# vewa-lfos.net
KiCad netlist of a schematic drawn in EAGLE
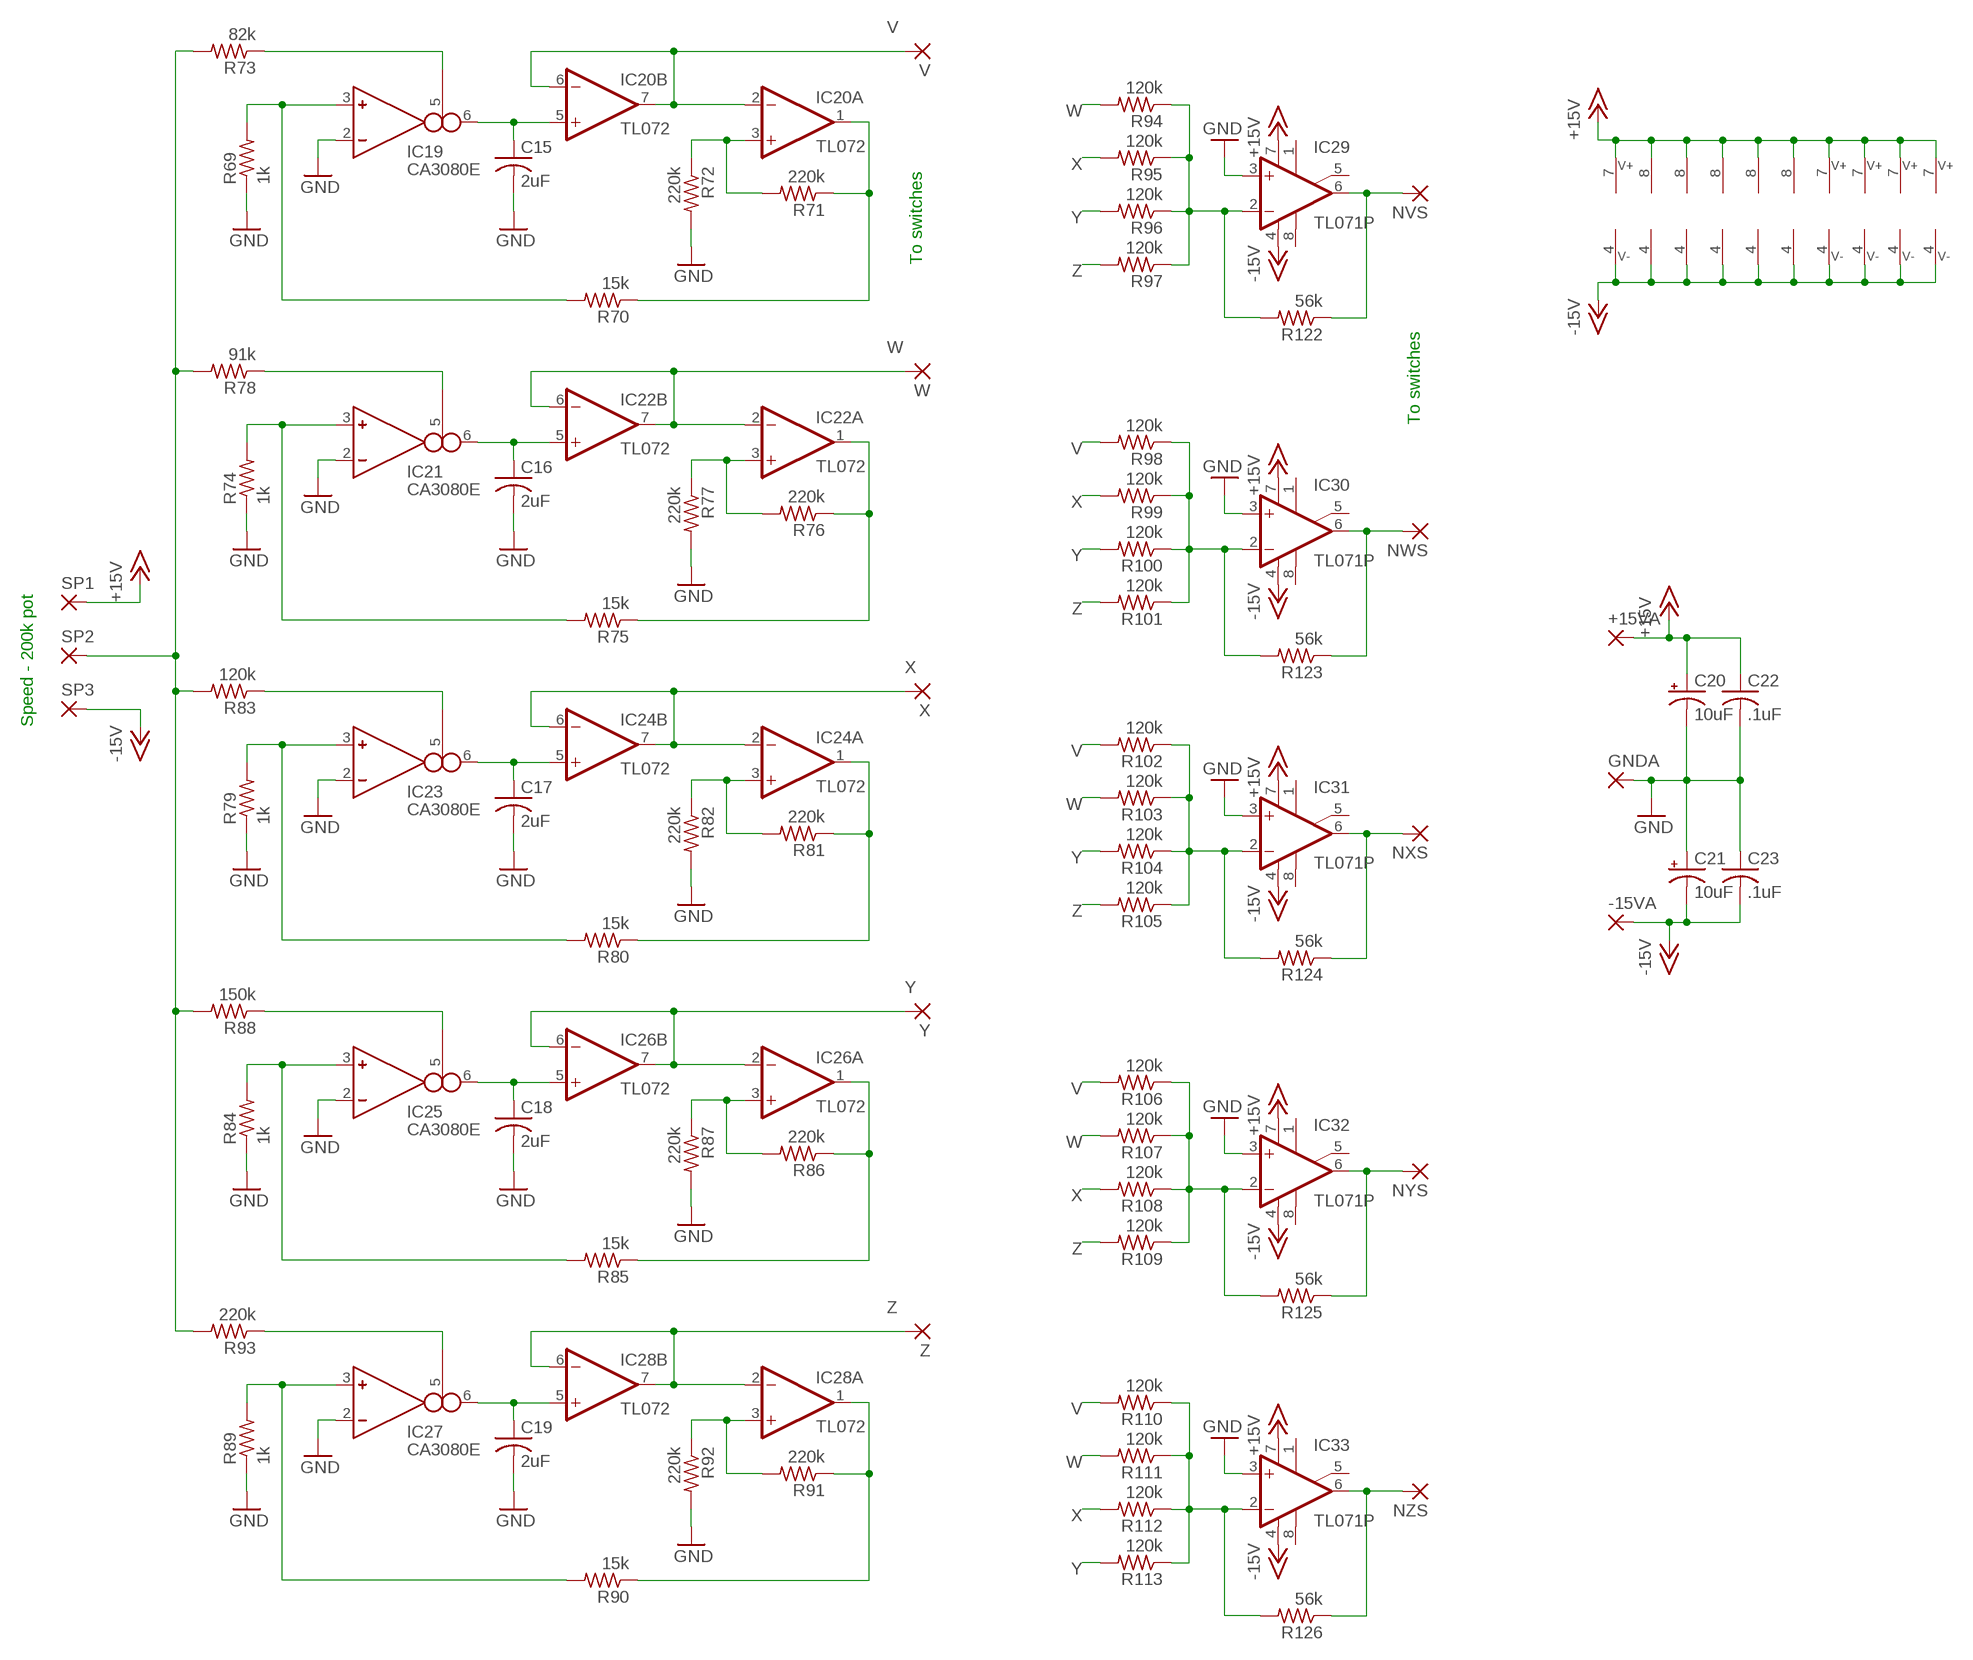
[diagram p0: schematic, sheet 1]

(export (version "E")
  (design (tool "Eeschema 10.0.6"))
  (components
    (comp (ref "+15VA")
      (value "2,54/1,0")
      (footprint "eagle-import:2,54_1,0")
      (libsource (lib "eagle-import") (part "2,54/1,0"))
    )
    (comp (ref "-15VA")
      (value "2,54/1,0")
      (footprint "eagle-import:2,54_1,0")
      (libsource (lib "eagle-import") (part "2,54/1,0"))
    )
    (comp (ref "C15")
      (value "2uF")
      (footprint "eagle-import:C050-025X075")
      (libsource (lib "eagle-import") (part "C-US050-025X075"))
    )
    (comp (ref "C16")
      (value "2uF")
      (footprint "eagle-import:C050-025X075")
      (libsource (lib "eagle-import") (part "C-US050-025X075"))
    )
    (comp (ref "C17")
      (value "2uF")
      (footprint "eagle-import:C050-025X075")
      (libsource (lib "eagle-import") (part "C-US050-025X075"))
    )
    (comp (ref "C18")
      (value "2uF")
      (footprint "eagle-import:C050-025X075")
      (libsource (lib "eagle-import") (part "C-US050-025X075"))
    )
    (comp (ref "C19")
      (value "2uF")
      (footprint "eagle-import:C050-025X075")
      (libsource (lib "eagle-import") (part "C-US050-025X075"))
    )
    (comp (ref "C20")
      (value "10uF")
      (footprint "eagle-import:E2,5-5")
      (libsource (lib "eagle-import") (part "CPOL-USE2.5-5"))
    )
    (comp (ref "C21")
      (value "10uF")
      (footprint "eagle-import:E2,5-5")
      (libsource (lib "eagle-import") (part "CPOL-USE2.5-5"))
    )
    (comp (ref "C22")
      (value ".1uF")
      (footprint "eagle-import:C050-025X075")
      (libsource (lib "eagle-import") (part "C-US050-025X075"))
    )
    (comp (ref "C23")
      (value ".1uF")
      (footprint "eagle-import:C050-025X075")
      (libsource (lib "eagle-import") (part "C-US050-025X075"))
    )
    (comp (ref "GNDA")
      (value "2,54/1,0")
      (footprint "eagle-import:2,54_1,0")
      (libsource (lib "eagle-import") (part "2,54/1,0"))
    )
    (comp (ref "IC19")
      (value "CA3080E")
      (footprint "eagle-import:DIL08")
      (libsource (lib "eagle-import") (part "CA3080E"))
    )
    (comp (ref "IC20")
      (value "TL072")
      (footprint "eagle-import:DIL08")
      (libsource (lib "eagle-import") (part "TL072-TOPP"))
    )
    (comp (ref "IC21")
      (value "CA3080E")
      (footprint "eagle-import:DIL08")
      (libsource (lib "eagle-import") (part "CA3080E"))
    )
    (comp (ref "IC22")
      (value "TL072")
      (footprint "eagle-import:DIL08")
      (libsource (lib "eagle-import") (part "TL072-TOPP"))
    )
    (comp (ref "IC23")
      (value "CA3080E")
      (footprint "eagle-import:DIL08")
      (libsource (lib "eagle-import") (part "CA3080E"))
    )
    (comp (ref "IC24")
      (value "TL072")
      (footprint "eagle-import:DIL08")
      (libsource (lib "eagle-import") (part "TL072-TOPP"))
    )
    (comp (ref "IC25")
      (value "CA3080E")
      (footprint "eagle-import:DIL08")
      (libsource (lib "eagle-import") (part "CA3080E"))
    )
    (comp (ref "IC26")
      (value "TL072")
      (footprint "eagle-import:DIL08")
      (libsource (lib "eagle-import") (part "TL072-TOPP"))
    )
    (comp (ref "IC27")
      (value "CA3080E")
      (footprint "eagle-import:DIL08")
      (libsource (lib "eagle-import") (part "CA3080E"))
    )
    (comp (ref "IC28")
      (value "TL072")
      (footprint "eagle-import:DIL08")
      (libsource (lib "eagle-import") (part "TL072-TOPP"))
    )
    (comp (ref "IC29")
      (value "TL071P")
      (footprint "eagle-import:DIL08")
      (libsource (lib "eagle-import") (part "TL071P"))
    )
    (comp (ref "IC30")
      (value "TL071P")
      (footprint "eagle-import:DIL08")
      (libsource (lib "eagle-import") (part "TL071P"))
    )
    (comp (ref "IC31")
      (value "TL071P")
      (footprint "eagle-import:DIL08")
      (libsource (lib "eagle-import") (part "TL071P"))
    )
    (comp (ref "IC32")
      (value "TL071P")
      (footprint "eagle-import:DIL08")
      (libsource (lib "eagle-import") (part "TL071P"))
    )
    (comp (ref "IC33")
      (value "TL071P")
      (footprint "eagle-import:DIL08")
      (libsource (lib "eagle-import") (part "TL071P"))
    )
    (comp (ref "NVS")
      (value "2,54/1,0")
      (footprint "eagle-import:2,54_1,0")
      (libsource (lib "eagle-import") (part "2,54/1,0"))
    )
    (comp (ref "NWS")
      (value "2,54/1,0")
      (footprint "eagle-import:2,54_1,0")
      (libsource (lib "eagle-import") (part "2,54/1,0"))
    )
    (comp (ref "NXS")
      (value "2,54/1,0")
      (footprint "eagle-import:2,54_1,0")
      (libsource (lib "eagle-import") (part "2,54/1,0"))
    )
    (comp (ref "NYS")
      (value "2,54/1,0")
      (footprint "eagle-import:2,54_1,0")
      (libsource (lib "eagle-import") (part "2,54/1,0"))
    )
    (comp (ref "NZS")
      (value "2,54/1,0")
      (footprint "eagle-import:2,54_1,0")
      (libsource (lib "eagle-import") (part "2,54/1,0"))
    )
    (comp (ref "R69")
      (value "1k")
      (footprint "eagle-import:0207_10")
      (libsource (lib "eagle-import") (part "R-US_0207/10"))
    )
    (comp (ref "R70")
      (value "15k")
      (footprint "eagle-import:0207_10")
      (libsource (lib "eagle-import") (part "R-US_0207/10"))
    )
    (comp (ref "R71")
      (value "220k")
      (footprint "eagle-import:0207_10")
      (libsource (lib "eagle-import") (part "R-US_0207/10"))
    )
    (comp (ref "R72")
      (value "220k")
      (footprint "eagle-import:0207_10")
      (libsource (lib "eagle-import") (part "R-US_0207/10"))
    )
    (comp (ref "R73")
      (value "82k")
      (footprint "eagle-import:0207_10")
      (libsource (lib "eagle-import") (part "R-US_0207/10"))
    )
    (comp (ref "R74")
      (value "1k")
      (footprint "eagle-import:0207_10")
      (libsource (lib "eagle-import") (part "R-US_0207/10"))
    )
    (comp (ref "R75")
      (value "15k")
      (footprint "eagle-import:0207_10")
      (libsource (lib "eagle-import") (part "R-US_0207/10"))
    )
    (comp (ref "R76")
      (value "220k")
      (footprint "eagle-import:0207_10")
      (libsource (lib "eagle-import") (part "R-US_0207/10"))
    )
    (comp (ref "R77")
      (value "220k")
      (footprint "eagle-import:0207_10")
      (libsource (lib "eagle-import") (part "R-US_0207/10"))
    )
    (comp (ref "R78")
      (value "91k")
      (footprint "eagle-import:0207_10")
      (libsource (lib "eagle-import") (part "R-US_0207/10"))
    )
    (comp (ref "R79")
      (value "1k")
      (footprint "eagle-import:0207_10")
      (libsource (lib "eagle-import") (part "R-US_0207/10"))
    )
    (comp (ref "R80")
      (value "15k")
      (footprint "eagle-import:0207_10")
      (libsource (lib "eagle-import") (part "R-US_0207/10"))
    )
    (comp (ref "R81")
      (value "220k")
      (footprint "eagle-import:0207_10")
      (libsource (lib "eagle-import") (part "R-US_0207/10"))
    )
    (comp (ref "R82")
      (value "220k")
      (footprint "eagle-import:0207_10")
      (libsource (lib "eagle-import") (part "R-US_0207/10"))
    )
    (comp (ref "R83")
      (value "120k")
      (footprint "eagle-import:0207_10")
      (libsource (lib "eagle-import") (part "R-US_0207/10"))
    )
    (comp (ref "R84")
      (value "1k")
      (footprint "eagle-import:0207_10")
      (libsource (lib "eagle-import") (part "R-US_0207/10"))
    )
    (comp (ref "R85")
      (value "15k")
      (footprint "eagle-import:0207_10")
      (libsource (lib "eagle-import") (part "R-US_0207/10"))
    )
    (comp (ref "R86")
      (value "220k")
      (footprint "eagle-import:0207_10")
      (libsource (lib "eagle-import") (part "R-US_0207/10"))
    )
    (comp (ref "R87")
      (value "220k")
      (footprint "eagle-import:0207_10")
      (libsource (lib "eagle-import") (part "R-US_0207/10"))
    )
    (comp (ref "R88")
      (value "150k")
      (footprint "eagle-import:0207_10")
      (libsource (lib "eagle-import") (part "R-US_0207/10"))
    )
    (comp (ref "R89")
      (value "1k")
      (footprint "eagle-import:0207_10")
      (libsource (lib "eagle-import") (part "R-US_0207/10"))
    )
    (comp (ref "R90")
      (value "15k")
      (footprint "eagle-import:0207_10")
      (libsource (lib "eagle-import") (part "R-US_0207/10"))
    )
    (comp (ref "R91")
      (value "220k")
      (footprint "eagle-import:0207_10")
      (libsource (lib "eagle-import") (part "R-US_0207/10"))
    )
    (comp (ref "R92")
      (value "220k")
      (footprint "eagle-import:0207_10")
      (libsource (lib "eagle-import") (part "R-US_0207/10"))
    )
    (comp (ref "R93")
      (value "220k")
      (footprint "eagle-import:0207_10")
      (libsource (lib "eagle-import") (part "R-US_0207/10"))
    )
    (comp (ref "R94")
      (value "120k")
      (footprint "eagle-import:0207_10")
      (libsource (lib "eagle-import") (part "R-US_0207/10"))
    )
    (comp (ref "R95")
      (value "120k")
      (footprint "eagle-import:0207_10")
      (libsource (lib "eagle-import") (part "R-US_0207/10"))
    )
    (comp (ref "R96")
      (value "120k")
      (footprint "eagle-import:0207_10")
      (libsource (lib "eagle-import") (part "R-US_0207/10"))
    )
    (comp (ref "R97")
      (value "120k")
      (footprint "eagle-import:0207_10")
      (libsource (lib "eagle-import") (part "R-US_0207/10"))
    )
    (comp (ref "R98")
      (value "120k")
      (footprint "eagle-import:0207_10")
      (libsource (lib "eagle-import") (part "R-US_0207/10"))
    )
    (comp (ref "R99")
      (value "120k")
      (footprint "eagle-import:0207_10")
      (libsource (lib "eagle-import") (part "R-US_0207/10"))
    )
    (comp (ref "R100")
      (value "120k")
      (footprint "eagle-import:0207_10")
      (libsource (lib "eagle-import") (part "R-US_0207/10"))
    )
    (comp (ref "R101")
      (value "120k")
      (footprint "eagle-import:0207_10")
      (libsource (lib "eagle-import") (part "R-US_0207/10"))
    )
    (comp (ref "R102")
      (value "120k")
      (footprint "eagle-import:0207_10")
      (libsource (lib "eagle-import") (part "R-US_0207/10"))
    )
    (comp (ref "R103")
      (value "120k")
      (footprint "eagle-import:0207_10")
      (libsource (lib "eagle-import") (part "R-US_0207/10"))
    )
    (comp (ref "R104")
      (value "120k")
      (footprint "eagle-import:0207_10")
      (libsource (lib "eagle-import") (part "R-US_0207/10"))
    )
    (comp (ref "R105")
      (value "120k")
      (footprint "eagle-import:0207_10")
      (libsource (lib "eagle-import") (part "R-US_0207/10"))
    )
    (comp (ref "R106")
      (value "120k")
      (footprint "eagle-import:0207_10")
      (libsource (lib "eagle-import") (part "R-US_0207/10"))
    )
    (comp (ref "R107")
      (value "120k")
      (footprint "eagle-import:0207_10")
      (libsource (lib "eagle-import") (part "R-US_0207/10"))
    )
    (comp (ref "R108")
      (value "120k")
      (footprint "eagle-import:0207_10")
      (libsource (lib "eagle-import") (part "R-US_0207/10"))
    )
    (comp (ref "R109")
      (value "120k")
      (footprint "eagle-import:0207_10")
      (libsource (lib "eagle-import") (part "R-US_0207/10"))
    )
    (comp (ref "R110")
      (value "120k")
      (footprint "eagle-import:0207_10")
      (libsource (lib "eagle-import") (part "R-US_0207/10"))
    )
    (comp (ref "R111")
      (value "120k")
      (footprint "eagle-import:0207_10")
      (libsource (lib "eagle-import") (part "R-US_0207/10"))
    )
    (comp (ref "R112")
      (value "120k")
      (footprint "eagle-import:0207_10")
      (libsource (lib "eagle-import") (part "R-US_0207/10"))
    )
    (comp (ref "R113")
      (value "120k")
      (footprint "eagle-import:0207_10")
      (libsource (lib "eagle-import") (part "R-US_0207/10"))
    )
    (comp (ref "R122")
      (value "56k")
      (footprint "eagle-import:0207_10")
      (libsource (lib "eagle-import") (part "R-US_0207/10"))
    )
    (comp (ref "R123")
      (value "56k")
      (footprint "eagle-import:0207_10")
      (libsource (lib "eagle-import") (part "R-US_0207/10"))
    )
    (comp (ref "R124")
      (value "56k")
      (footprint "eagle-import:0207_10")
      (libsource (lib "eagle-import") (part "R-US_0207/10"))
    )
    (comp (ref "R125")
      (value "56k")
      (footprint "eagle-import:0207_10")
      (libsource (lib "eagle-import") (part "R-US_0207/10"))
    )
    (comp (ref "R126")
      (value "56k")
      (footprint "eagle-import:0207_10")
      (libsource (lib "eagle-import") (part "R-US_0207/10"))
    )
    (comp (ref "SP1")
      (value "2,54/1,0")
      (footprint "eagle-import:2,54_1,0")
      (libsource (lib "eagle-import") (part "2,54/1,0"))
    )
    (comp (ref "SP2")
      (value "2,54/1,0")
      (footprint "eagle-import:2,54_1,0")
      (libsource (lib "eagle-import") (part "2,54/1,0"))
    )
    (comp (ref "SP3")
      (value "2,54/1,0")
      (footprint "eagle-import:2,54_1,0")
      (libsource (lib "eagle-import") (part "2,54/1,0"))
    )
    (comp (ref "V")
      (value "2,54/1,0")
      (footprint "eagle-import:2,54_1,0")
      (libsource (lib "eagle-import") (part "2,54/1,0"))
    )
    (comp (ref "W")
      (value "2,54/1,0")
      (footprint "eagle-import:2,54_1,0")
      (libsource (lib "eagle-import") (part "2,54/1,0"))
    )
    (comp (ref "X")
      (value "2,54/1,0")
      (footprint "eagle-import:2,54_1,0")
      (libsource (lib "eagle-import") (part "2,54/1,0"))
    )
    (comp (ref "Y")
      (value "2,54/1,0")
      (footprint "eagle-import:2,54_1,0")
      (libsource (lib "eagle-import") (part "2,54/1,0"))
    )
    (comp (ref "Z")
      (value "2,54/1,0")
      (footprint "eagle-import:2,54_1,0")
      (libsource (lib "eagle-import") (part "2,54/1,0"))
    )
  )
  (nets
    (net (code "1") (name "+15V") (class "Default")
      (node (ref "+15VA") (pin "1") (pinfunction "P_1") (pintype "passive"))
      (node (ref "C20") (pin "+") (pinfunction "+_+") (pintype "passive"))
      (node (ref "C22") (pin "1") (pinfunction "1_1") (pintype "passive"))
      (node (ref "IC19") (pin "7") (pinfunction "7_7") (pintype "passive"))
      (node (ref "IC20") (pin "8") (pinfunction "V+_8") (pintype "power_in"))
      (node (ref "IC21") (pin "7") (pinfunction "7_7") (pintype "passive"))
      (node (ref "IC22") (pin "8") (pinfunction "V+_8") (pintype "power_in"))
      (node (ref "IC23") (pin "7") (pinfunction "7_7") (pintype "passive"))
      (node (ref "IC24") (pin "8") (pinfunction "V+_8") (pintype "power_in"))
      (node (ref "IC25") (pin "7") (pinfunction "7_7") (pintype "passive"))
      (node (ref "IC26") (pin "8") (pinfunction "V+_8") (pintype "power_in"))
      (node (ref "IC27") (pin "7") (pinfunction "7_7") (pintype "passive"))
      (node (ref "IC28") (pin "8") (pinfunction "V+_8") (pintype "power_in"))
      (node (ref "IC29") (pin "7") (pinfunction "V+_7") (pintype "power_in"))
      (node (ref "IC30") (pin "7") (pinfunction "V+_7") (pintype "power_in"))
      (node (ref "IC31") (pin "7") (pinfunction "V+_7") (pintype "power_in"))
      (node (ref "IC32") (pin "7") (pinfunction "V+_7") (pintype "power_in"))
      (node (ref "IC33") (pin "7") (pinfunction "V+_7") (pintype "power_in"))
      (node (ref "SP1") (pin "1") (pinfunction "P_1") (pintype "passive"))
    )
    (net (code "2") (name "-15V") (class "Default")
      (node (ref "-15VA") (pin "1") (pinfunction "P_1") (pintype "passive"))
      (node (ref "C21") (pin "-") (pinfunction "-_-") (pintype "passive"))
      (node (ref "C23") (pin "2") (pinfunction "2_2") (pintype "passive"))
      (node (ref "IC19") (pin "4") (pinfunction "4_4") (pintype "passive"))
      (node (ref "IC20") (pin "4") (pinfunction "V-_4") (pintype "power_in"))
      (node (ref "IC21") (pin "4") (pinfunction "4_4") (pintype "passive"))
      (node (ref "IC22") (pin "4") (pinfunction "V-_4") (pintype "power_in"))
      (node (ref "IC23") (pin "4") (pinfunction "4_4") (pintype "passive"))
      (node (ref "IC24") (pin "4") (pinfunction "V-_4") (pintype "power_in"))
      (node (ref "IC25") (pin "4") (pinfunction "4_4") (pintype "passive"))
      (node (ref "IC26") (pin "4") (pinfunction "V-_4") (pintype "power_in"))
      (node (ref "IC27") (pin "4") (pinfunction "4_4") (pintype "passive"))
      (node (ref "IC28") (pin "4") (pinfunction "V-_4") (pintype "power_in"))
      (node (ref "IC29") (pin "4") (pinfunction "V-_4") (pintype "power_in"))
      (node (ref "IC30") (pin "4") (pinfunction "V-_4") (pintype "power_in"))
      (node (ref "IC31") (pin "4") (pinfunction "V-_4") (pintype "power_in"))
      (node (ref "IC32") (pin "4") (pinfunction "V-_4") (pintype "power_in"))
      (node (ref "IC33") (pin "4") (pinfunction "V-_4") (pintype "power_in"))
      (node (ref "SP3") (pin "1") (pinfunction "P_1") (pintype "passive"))
    )
    (net (code "3") (name "/V") (class "Default")
      (node (ref "IC20") (pin "2") (pinfunction "-IN_2") (pintype "input"))
      (node (ref "IC20") (pin "6") (pinfunction "-IN_6") (pintype "input"))
      (node (ref "IC20") (pin "7") (pinfunction "OUT_7") (pintype "output"))
      (node (ref "R102") (pin "2") (pinfunction "2_2") (pintype "passive"))
      (node (ref "R106") (pin "2") (pinfunction "2_2") (pintype "passive"))
      (node (ref "R110") (pin "2") (pinfunction "2_2") (pintype "passive"))
      (node (ref "R98") (pin "2") (pinfunction "2_2") (pintype "passive"))
      (node (ref "V") (pin "1") (pinfunction "P_1") (pintype "passive"))
    )
    (net (code "4") (name "/W") (class "Default")
      (node (ref "IC22") (pin "2") (pinfunction "-IN_2") (pintype "input"))
      (node (ref "IC22") (pin "6") (pinfunction "-IN_6") (pintype "input"))
      (node (ref "IC22") (pin "7") (pinfunction "OUT_7") (pintype "output"))
      (node (ref "R103") (pin "2") (pinfunction "2_2") (pintype "passive"))
      (node (ref "R107") (pin "2") (pinfunction "2_2") (pintype "passive"))
      (node (ref "R111") (pin "2") (pinfunction "2_2") (pintype "passive"))
      (node (ref "R94") (pin "2") (pinfunction "2_2") (pintype "passive"))
      (node (ref "W") (pin "1") (pinfunction "P_1") (pintype "passive"))
    )
    (net (code "5") (name "/X") (class "Default")
      (node (ref "IC24") (pin "2") (pinfunction "-IN_2") (pintype "input"))
      (node (ref "IC24") (pin "6") (pinfunction "-IN_6") (pintype "input"))
      (node (ref "IC24") (pin "7") (pinfunction "OUT_7") (pintype "output"))
      (node (ref "R108") (pin "2") (pinfunction "2_2") (pintype "passive"))
      (node (ref "R112") (pin "2") (pinfunction "2_2") (pintype "passive"))
      (node (ref "R95") (pin "2") (pinfunction "2_2") (pintype "passive"))
      (node (ref "R99") (pin "2") (pinfunction "2_2") (pintype "passive"))
      (node (ref "X") (pin "1") (pinfunction "P_1") (pintype "passive"))
    )
    (net (code "6") (name "/Y") (class "Default")
      (node (ref "IC26") (pin "2") (pinfunction "-IN_2") (pintype "input"))
      (node (ref "IC26") (pin "6") (pinfunction "-IN_6") (pintype "input"))
      (node (ref "IC26") (pin "7") (pinfunction "OUT_7") (pintype "output"))
      (node (ref "R100") (pin "2") (pinfunction "2_2") (pintype "passive"))
      (node (ref "R104") (pin "2") (pinfunction "2_2") (pintype "passive"))
      (node (ref "R113") (pin "2") (pinfunction "2_2") (pintype "passive"))
      (node (ref "R96") (pin "2") (pinfunction "2_2") (pintype "passive"))
      (node (ref "Y") (pin "1") (pinfunction "P_1") (pintype "passive"))
    )
    (net (code "7") (name "/Z") (class "Default")
      (node (ref "IC28") (pin "2") (pinfunction "-IN_2") (pintype "input"))
      (node (ref "IC28") (pin "6") (pinfunction "-IN_6") (pintype "input"))
      (node (ref "IC28") (pin "7") (pinfunction "OUT_7") (pintype "output"))
      (node (ref "R101") (pin "2") (pinfunction "2_2") (pintype "passive"))
      (node (ref "R105") (pin "2") (pinfunction "2_2") (pintype "passive"))
      (node (ref "R109") (pin "2") (pinfunction "2_2") (pintype "passive"))
      (node (ref "R97") (pin "2") (pinfunction "2_2") (pintype "passive"))
      (node (ref "Z") (pin "1") (pinfunction "P_1") (pintype "passive"))
    )
    (net (code "8") (name "GND") (class "Default")
      (node (ref "C15") (pin "2") (pinfunction "2_2") (pintype "passive"))
      (node (ref "C16") (pin "2") (pinfunction "2_2") (pintype "passive"))
      (node (ref "C17") (pin "2") (pinfunction "2_2") (pintype "passive"))
      (node (ref "C18") (pin "2") (pinfunction "2_2") (pintype "passive"))
      (node (ref "C19") (pin "2") (pinfunction "2_2") (pintype "passive"))
      (node (ref "C20") (pin "-") (pinfunction "-_-") (pintype "passive"))
      (node (ref "C21") (pin "+") (pinfunction "+_+") (pintype "passive"))
      (node (ref "C22") (pin "2") (pinfunction "2_2") (pintype "passive"))
      (node (ref "C23") (pin "1") (pinfunction "1_1") (pintype "passive"))
      (node (ref "GNDA") (pin "1") (pinfunction "P_1") (pintype "passive"))
      (node (ref "IC19") (pin "2") (pinfunction "IN_N_2") (pintype "input"))
      (node (ref "IC21") (pin "2") (pinfunction "IN_N_2") (pintype "input"))
      (node (ref "IC23") (pin "2") (pinfunction "IN_N_2") (pintype "input"))
      (node (ref "IC25") (pin "2") (pinfunction "IN_N_2") (pintype "input"))
      (node (ref "IC27") (pin "2") (pinfunction "IN_N_2") (pintype "input"))
      (node (ref "IC29") (pin "3") (pinfunction "+IN_3") (pintype "input"))
      (node (ref "IC30") (pin "3") (pinfunction "+IN_3") (pintype "input"))
      (node (ref "IC31") (pin "3") (pinfunction "+IN_3") (pintype "input"))
      (node (ref "IC32") (pin "3") (pinfunction "+IN_3") (pintype "input"))
      (node (ref "IC33") (pin "3") (pinfunction "+IN_3") (pintype "input"))
      (node (ref "R69") (pin "1") (pinfunction "1_1") (pintype "passive"))
      (node (ref "R72") (pin "2") (pinfunction "2_2") (pintype "passive"))
      (node (ref "R74") (pin "1") (pinfunction "1_1") (pintype "passive"))
      (node (ref "R77") (pin "2") (pinfunction "2_2") (pintype "passive"))
      (node (ref "R79") (pin "1") (pinfunction "1_1") (pintype "passive"))
      (node (ref "R82") (pin "2") (pinfunction "2_2") (pintype "passive"))
      (node (ref "R84") (pin "1") (pinfunction "1_1") (pintype "passive"))
      (node (ref "R87") (pin "2") (pinfunction "2_2") (pintype "passive"))
      (node (ref "R89") (pin "1") (pinfunction "1_1") (pintype "passive"))
      (node (ref "R92") (pin "2") (pinfunction "2_2") (pintype "passive"))
    )
    (net (code "9") (name "Net-(IC19A-IN_P)") (class "Default")
      (node (ref "IC19") (pin "3") (pinfunction "IN_P_3") (pintype "input"))
      (node (ref "R69") (pin "2") (pinfunction "2_2") (pintype "passive"))
      (node (ref "R70") (pin "2") (pinfunction "2_2") (pintype "passive"))
    )
    (net (code "10") (name "Net-(IC19A-I_BIAS)") (class "Default")
      (node (ref "IC19") (pin "5") (pinfunction "I_BIAS_5") (pintype "input"))
      (node (ref "R73") (pin "1") (pinfunction "1_1") (pintype "passive"))
    )
    (net (code "11") (name "Net-(IC19A-OUT)") (class "Default")
      (node (ref "C15") (pin "1") (pinfunction "1_1") (pintype "passive"))
      (node (ref "IC19") (pin "6") (pinfunction "OUT_6") (pintype "output"))
      (node (ref "IC20") (pin "5") (pinfunction "+IN_5") (pintype "input"))
    )
    (net (code "12") (name "Net-(IC20A-+IN)") (class "Default")
      (node (ref "IC20") (pin "3") (pinfunction "+IN_3") (pintype "input"))
      (node (ref "R71") (pin "2") (pinfunction "2_2") (pintype "passive"))
      (node (ref "R72") (pin "1") (pinfunction "1_1") (pintype "passive"))
    )
    (net (code "13") (name "Net-(IC20A-OUT)") (class "Default")
      (node (ref "IC20") (pin "1") (pinfunction "OUT_1") (pintype "output"))
      (node (ref "R70") (pin "1") (pinfunction "1_1") (pintype "passive"))
      (node (ref "R71") (pin "1") (pinfunction "1_1") (pintype "passive"))
    )
    (net (code "14") (name "Net-(IC21A-IN_P)") (class "Default")
      (node (ref "IC21") (pin "3") (pinfunction "IN_P_3") (pintype "input"))
      (node (ref "R74") (pin "2") (pinfunction "2_2") (pintype "passive"))
      (node (ref "R75") (pin "2") (pinfunction "2_2") (pintype "passive"))
    )
    (net (code "15") (name "Net-(IC21A-I_BIAS)") (class "Default")
      (node (ref "IC21") (pin "5") (pinfunction "I_BIAS_5") (pintype "input"))
      (node (ref "R78") (pin "1") (pinfunction "1_1") (pintype "passive"))
    )
    (net (code "16") (name "Net-(IC21A-OUT)") (class "Default")
      (node (ref "C16") (pin "1") (pinfunction "1_1") (pintype "passive"))
      (node (ref "IC21") (pin "6") (pinfunction "OUT_6") (pintype "output"))
      (node (ref "IC22") (pin "5") (pinfunction "+IN_5") (pintype "input"))
    )
    (net (code "17") (name "Net-(IC22A-+IN)") (class "Default")
      (node (ref "IC22") (pin "3") (pinfunction "+IN_3") (pintype "input"))
      (node (ref "R76") (pin "2") (pinfunction "2_2") (pintype "passive"))
      (node (ref "R77") (pin "1") (pinfunction "1_1") (pintype "passive"))
    )
    (net (code "18") (name "Net-(IC22A-OUT)") (class "Default")
      (node (ref "IC22") (pin "1") (pinfunction "OUT_1") (pintype "output"))
      (node (ref "R75") (pin "1") (pinfunction "1_1") (pintype "passive"))
      (node (ref "R76") (pin "1") (pinfunction "1_1") (pintype "passive"))
    )
    (net (code "19") (name "Net-(IC23A-IN_P)") (class "Default")
      (node (ref "IC23") (pin "3") (pinfunction "IN_P_3") (pintype "input"))
      (node (ref "R79") (pin "2") (pinfunction "2_2") (pintype "passive"))
      (node (ref "R80") (pin "2") (pinfunction "2_2") (pintype "passive"))
    )
    (net (code "20") (name "Net-(IC23A-I_BIAS)") (class "Default")
      (node (ref "IC23") (pin "5") (pinfunction "I_BIAS_5") (pintype "input"))
      (node (ref "R83") (pin "1") (pinfunction "1_1") (pintype "passive"))
    )
    (net (code "21") (name "Net-(IC23A-OUT)") (class "Default")
      (node (ref "C17") (pin "1") (pinfunction "1_1") (pintype "passive"))
      (node (ref "IC23") (pin "6") (pinfunction "OUT_6") (pintype "output"))
      (node (ref "IC24") (pin "5") (pinfunction "+IN_5") (pintype "input"))
    )
    (net (code "22") (name "Net-(IC24A-+IN)") (class "Default")
      (node (ref "IC24") (pin "3") (pinfunction "+IN_3") (pintype "input"))
      (node (ref "R81") (pin "2") (pinfunction "2_2") (pintype "passive"))
      (node (ref "R82") (pin "1") (pinfunction "1_1") (pintype "passive"))
    )
    (net (code "23") (name "Net-(IC24A-OUT)") (class "Default")
      (node (ref "IC24") (pin "1") (pinfunction "OUT_1") (pintype "output"))
      (node (ref "R80") (pin "1") (pinfunction "1_1") (pintype "passive"))
      (node (ref "R81") (pin "1") (pinfunction "1_1") (pintype "passive"))
    )
    (net (code "24") (name "Net-(IC25A-IN_P)") (class "Default")
      (node (ref "IC25") (pin "3") (pinfunction "IN_P_3") (pintype "input"))
      (node (ref "R84") (pin "2") (pinfunction "2_2") (pintype "passive"))
      (node (ref "R85") (pin "2") (pinfunction "2_2") (pintype "passive"))
    )
    (net (code "25") (name "Net-(IC25A-I_BIAS)") (class "Default")
      (node (ref "IC25") (pin "5") (pinfunction "I_BIAS_5") (pintype "input"))
      (node (ref "R88") (pin "1") (pinfunction "1_1") (pintype "passive"))
    )
    (net (code "26") (name "Net-(IC25A-OUT)") (class "Default")
      (node (ref "C18") (pin "1") (pinfunction "1_1") (pintype "passive"))
      (node (ref "IC25") (pin "6") (pinfunction "OUT_6") (pintype "output"))
      (node (ref "IC26") (pin "5") (pinfunction "+IN_5") (pintype "input"))
    )
    (net (code "27") (name "Net-(IC26A-+IN)") (class "Default")
      (node (ref "IC26") (pin "3") (pinfunction "+IN_3") (pintype "input"))
      (node (ref "R86") (pin "2") (pinfunction "2_2") (pintype "passive"))
      (node (ref "R87") (pin "1") (pinfunction "1_1") (pintype "passive"))
    )
    (net (code "28") (name "Net-(IC26A-OUT)") (class "Default")
      (node (ref "IC26") (pin "1") (pinfunction "OUT_1") (pintype "output"))
      (node (ref "R85") (pin "1") (pinfunction "1_1") (pintype "passive"))
      (node (ref "R86") (pin "1") (pinfunction "1_1") (pintype "passive"))
    )
    (net (code "29") (name "Net-(IC27A-IN_P)") (class "Default")
      (node (ref "IC27") (pin "3") (pinfunction "IN_P_3") (pintype "input"))
      (node (ref "R89") (pin "2") (pinfunction "2_2") (pintype "passive"))
      (node (ref "R90") (pin "2") (pinfunction "2_2") (pintype "passive"))
    )
    (net (code "30") (name "Net-(IC27A-I_BIAS)") (class "Default")
      (node (ref "IC27") (pin "5") (pinfunction "I_BIAS_5") (pintype "input"))
      (node (ref "R93") (pin "1") (pinfunction "1_1") (pintype "passive"))
    )
    (net (code "31") (name "Net-(IC27A-OUT)") (class "Default")
      (node (ref "C19") (pin "1") (pinfunction "1_1") (pintype "passive"))
      (node (ref "IC27") (pin "6") (pinfunction "OUT_6") (pintype "output"))
      (node (ref "IC28") (pin "5") (pinfunction "+IN_5") (pintype "input"))
    )
    (net (code "32") (name "Net-(IC28A-+IN)") (class "Default")
      (node (ref "IC28") (pin "3") (pinfunction "+IN_3") (pintype "input"))
      (node (ref "R91") (pin "2") (pinfunction "2_2") (pintype "passive"))
      (node (ref "R92") (pin "1") (pinfunction "1_1") (pintype "passive"))
    )
    (net (code "33") (name "Net-(IC28A-OUT)") (class "Default")
      (node (ref "IC28") (pin "1") (pinfunction "OUT_1") (pintype "output"))
      (node (ref "R90") (pin "1") (pinfunction "1_1") (pintype "passive"))
      (node (ref "R91") (pin "1") (pinfunction "1_1") (pintype "passive"))
    )
    (net (code "34") (name "Net-(IC29--IN)") (class "Default")
      (node (ref "IC29") (pin "2") (pinfunction "-IN_2") (pintype "input"))
      (node (ref "R122") (pin "2") (pinfunction "2_2") (pintype "passive"))
      (node (ref "R94") (pin "1") (pinfunction "1_1") (pintype "passive"))
      (node (ref "R95") (pin "1") (pinfunction "1_1") (pintype "passive"))
      (node (ref "R96") (pin "1") (pinfunction "1_1") (pintype "passive"))
      (node (ref "R97") (pin "1") (pinfunction "1_1") (pintype "passive"))
    )
    (net (code "35") (name "Net-(IC29-OUT)") (class "Default")
      (node (ref "IC29") (pin "6") (pinfunction "OUT_6") (pintype "output"))
      (node (ref "NVS") (pin "1") (pinfunction "P_1") (pintype "passive"))
      (node (ref "R122") (pin "1") (pinfunction "1_1") (pintype "passive"))
    )
    (net (code "36") (name "Net-(IC30--IN)") (class "Default")
      (node (ref "IC30") (pin "2") (pinfunction "-IN_2") (pintype "input"))
      (node (ref "R100") (pin "1") (pinfunction "1_1") (pintype "passive"))
      (node (ref "R101") (pin "1") (pinfunction "1_1") (pintype "passive"))
      (node (ref "R123") (pin "2") (pinfunction "2_2") (pintype "passive"))
      (node (ref "R98") (pin "1") (pinfunction "1_1") (pintype "passive"))
      (node (ref "R99") (pin "1") (pinfunction "1_1") (pintype "passive"))
    )
    (net (code "37") (name "Net-(IC30-OUT)") (class "Default")
      (node (ref "IC30") (pin "6") (pinfunction "OUT_6") (pintype "output"))
      (node (ref "NWS") (pin "1") (pinfunction "P_1") (pintype "passive"))
      (node (ref "R123") (pin "1") (pinfunction "1_1") (pintype "passive"))
    )
    (net (code "38") (name "Net-(IC31--IN)") (class "Default")
      (node (ref "IC31") (pin "2") (pinfunction "-IN_2") (pintype "input"))
      (node (ref "R102") (pin "1") (pinfunction "1_1") (pintype "passive"))
      (node (ref "R103") (pin "1") (pinfunction "1_1") (pintype "passive"))
      (node (ref "R104") (pin "1") (pinfunction "1_1") (pintype "passive"))
      (node (ref "R105") (pin "1") (pinfunction "1_1") (pintype "passive"))
      (node (ref "R124") (pin "2") (pinfunction "2_2") (pintype "passive"))
    )
    (net (code "39") (name "Net-(IC31-OUT)") (class "Default")
      (node (ref "IC31") (pin "6") (pinfunction "OUT_6") (pintype "output"))
      (node (ref "NXS") (pin "1") (pinfunction "P_1") (pintype "passive"))
      (node (ref "R124") (pin "1") (pinfunction "1_1") (pintype "passive"))
    )
    (net (code "40") (name "Net-(IC32--IN)") (class "Default")
      (node (ref "IC32") (pin "2") (pinfunction "-IN_2") (pintype "input"))
      (node (ref "R106") (pin "1") (pinfunction "1_1") (pintype "passive"))
      (node (ref "R107") (pin "1") (pinfunction "1_1") (pintype "passive"))
      (node (ref "R108") (pin "1") (pinfunction "1_1") (pintype "passive"))
      (node (ref "R109") (pin "1") (pinfunction "1_1") (pintype "passive"))
      (node (ref "R125") (pin "2") (pinfunction "2_2") (pintype "passive"))
    )
    (net (code "41") (name "Net-(IC32-OUT)") (class "Default")
      (node (ref "IC32") (pin "6") (pinfunction "OUT_6") (pintype "output"))
      (node (ref "NYS") (pin "1") (pinfunction "P_1") (pintype "passive"))
      (node (ref "R125") (pin "1") (pinfunction "1_1") (pintype "passive"))
    )
    (net (code "42") (name "Net-(IC33--IN)") (class "Default")
      (node (ref "IC33") (pin "2") (pinfunction "-IN_2") (pintype "input"))
      (node (ref "R110") (pin "1") (pinfunction "1_1") (pintype "passive"))
      (node (ref "R111") (pin "1") (pinfunction "1_1") (pintype "passive"))
      (node (ref "R112") (pin "1") (pinfunction "1_1") (pintype "passive"))
      (node (ref "R113") (pin "1") (pinfunction "1_1") (pintype "passive"))
      (node (ref "R126") (pin "2") (pinfunction "2_2") (pintype "passive"))
    )
    (net (code "43") (name "Net-(IC33-OUT)") (class "Default")
      (node (ref "IC33") (pin "6") (pinfunction "OUT_6") (pintype "output"))
      (node (ref "NZS") (pin "1") (pinfunction "P_1") (pintype "passive"))
      (node (ref "R126") (pin "1") (pinfunction "1_1") (pintype "passive"))
    )
    (net (code "44") (name "Net-(SP2-P)") (class "Default")
      (node (ref "R73") (pin "2") (pinfunction "2_2") (pintype "passive"))
      (node (ref "R78") (pin "2") (pinfunction "2_2") (pintype "passive"))
      (node (ref "R83") (pin "2") (pinfunction "2_2") (pintype "passive"))
      (node (ref "R88") (pin "2") (pinfunction "2_2") (pintype "passive"))
      (node (ref "R93") (pin "2") (pinfunction "2_2") (pintype "passive"))
      (node (ref "SP2") (pin "1") (pinfunction "P_1") (pintype "passive"))
    )
    (net (code "45") (name "unconnected-(IC29-ON1-Pad1)") (class "Default")
      (node (ref "IC29") (pin "1") (pinfunction "ON1_1") (pintype "passive"))
    )
    (net (code "46") (name "unconnected-(IC29-ON2-Pad5)") (class "Default")
      (node (ref "IC29") (pin "5") (pinfunction "ON2_5") (pintype "passive"))
    )
    (net (code "47") (name "unconnected-(IC29-OPT-Pad8)") (class "Default")
      (node (ref "IC29") (pin "8") (pinfunction "OPT_8") (pintype "passive"))
    )
    (net (code "48") (name "unconnected-(IC30-ON1-Pad1)") (class "Default")
      (node (ref "IC30") (pin "1") (pinfunction "ON1_1") (pintype "passive"))
    )
    (net (code "49") (name "unconnected-(IC30-ON2-Pad5)") (class "Default")
      (node (ref "IC30") (pin "5") (pinfunction "ON2_5") (pintype "passive"))
    )
    (net (code "50") (name "unconnected-(IC30-OPT-Pad8)") (class "Default")
      (node (ref "IC30") (pin "8") (pinfunction "OPT_8") (pintype "passive"))
    )
    (net (code "51") (name "unconnected-(IC31-ON1-Pad1)") (class "Default")
      (node (ref "IC31") (pin "1") (pinfunction "ON1_1") (pintype "passive"))
    )
    (net (code "52") (name "unconnected-(IC31-ON2-Pad5)") (class "Default")
      (node (ref "IC31") (pin "5") (pinfunction "ON2_5") (pintype "passive"))
    )
    (net (code "53") (name "unconnected-(IC31-OPT-Pad8)") (class "Default")
      (node (ref "IC31") (pin "8") (pinfunction "OPT_8") (pintype "passive"))
    )
    (net (code "54") (name "unconnected-(IC32-ON1-Pad1)") (class "Default")
      (node (ref "IC32") (pin "1") (pinfunction "ON1_1") (pintype "passive"))
    )
    (net (code "55") (name "unconnected-(IC32-ON2-Pad5)") (class "Default")
      (node (ref "IC32") (pin "5") (pinfunction "ON2_5") (pintype "passive"))
    )
    (net (code "56") (name "unconnected-(IC32-OPT-Pad8)") (class "Default")
      (node (ref "IC32") (pin "8") (pinfunction "OPT_8") (pintype "passive"))
    )
    (net (code "57") (name "unconnected-(IC33-ON1-Pad1)") (class "Default")
      (node (ref "IC33") (pin "1") (pinfunction "ON1_1") (pintype "passive"))
    )
    (net (code "58") (name "unconnected-(IC33-ON2-Pad5)") (class "Default")
      (node (ref "IC33") (pin "5") (pinfunction "ON2_5") (pintype "passive"))
    )
    (net (code "59") (name "unconnected-(IC33-OPT-Pad8)") (class "Default")
      (node (ref "IC33") (pin "8") (pinfunction "OPT_8") (pintype "passive"))
    )
  )
)
